# receiver_1.net
KiCad netlist of a schematic drawn in Altium Designer
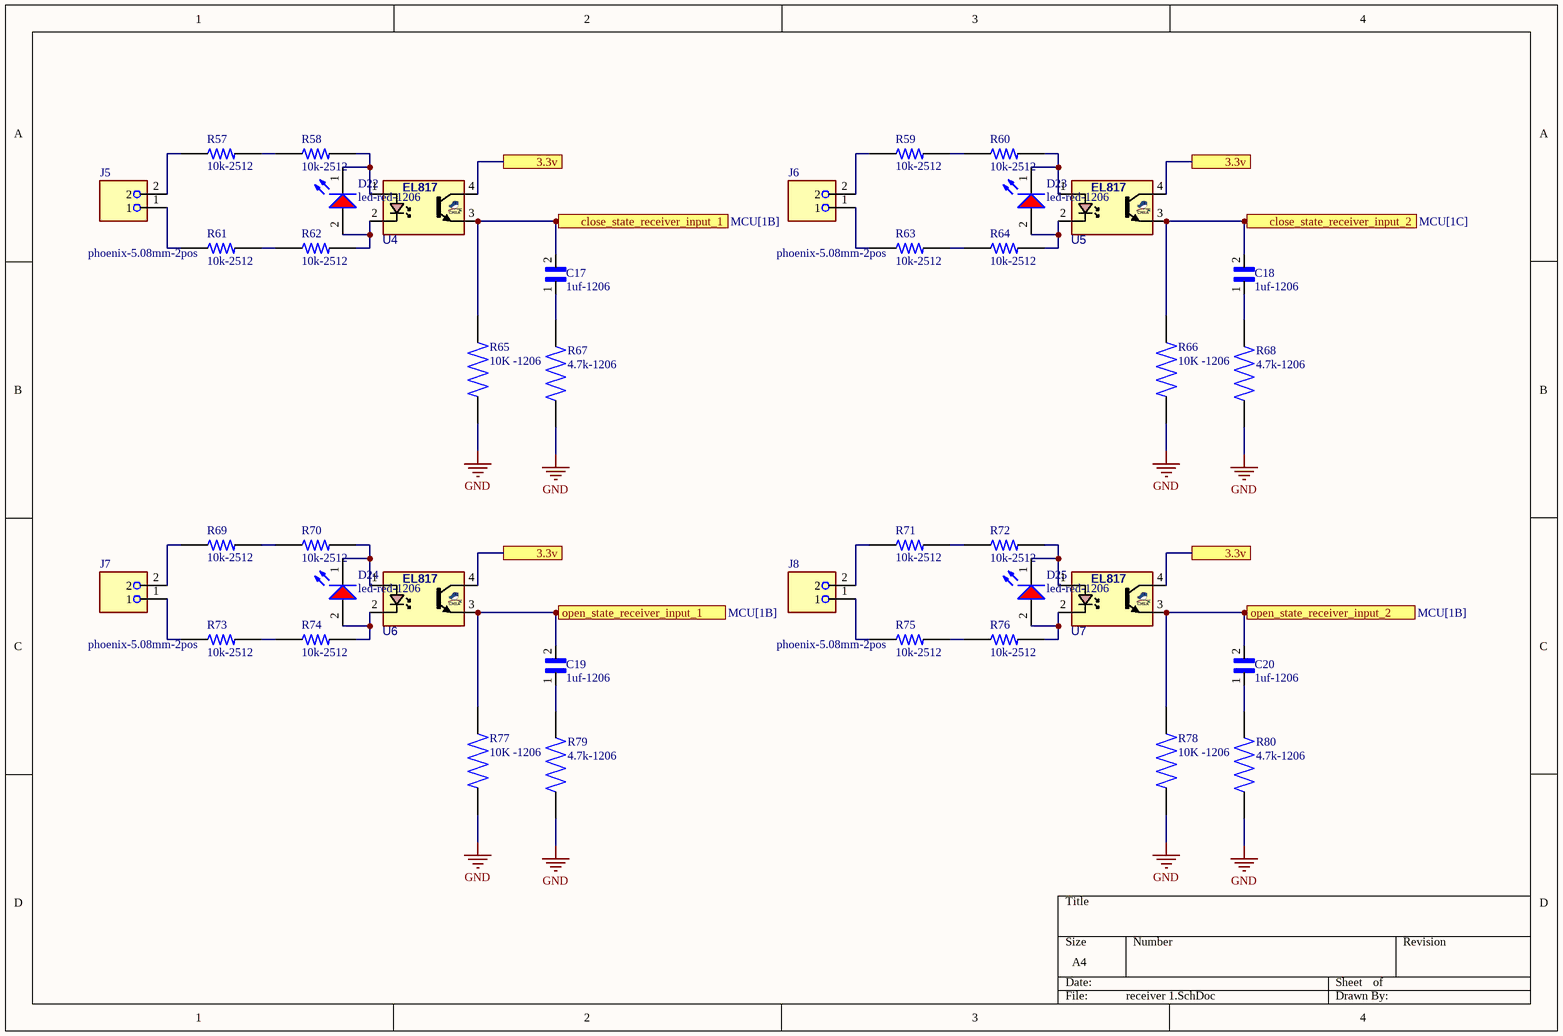
[diagram p0: receiver 1.SchDoc]

(export (version "E")
  (design (tool "Eeschema 10.0.6"))
  (components
    (comp (ref "C17")
      (value "1uf-1206")
      (footprint "CAPC3216X180N")
      (description "1ÂµF Â±20% 50V Ceramic Capacitor X8R 1206 (3216 Metric)")
      (fields (field (name "MF") "TDK") (field (name "MP") "CGA5L3X8R1H105M160AB"))
      (libsource (lib "cap-1206") (part "CGA5L3X8R1H105M160AB"))
    )
    (comp (ref "C18")
      (value "1uf-1206")
      (footprint "CAPC3216X180N")
      (description "1ÂµF Â±20% 50V Ceramic Capacitor X8R 1206 (3216 Metric)")
      (fields (field (name "MF") "TDK") (field (name "MP") "CGA5L3X8R1H105M160AB"))
      (libsource (lib "cap-1206") (part "CGA5L3X8R1H105M160AB"))
    )
    (comp (ref "C19")
      (value "1uf-1206")
      (footprint "CAPC3216X180N")
      (description "1ÂµF Â±20% 50V Ceramic Capacitor X8R 1206 (3216 Metric)")
      (fields (field (name "MF") "TDK") (field (name "MP") "CGA5L3X8R1H105M160AB"))
      (libsource (lib "cap-1206") (part "CGA5L3X8R1H105M160AB"))
    )
    (comp (ref "C20")
      (value "1uf-1206")
      (footprint "CAPC3216X180N")
      (description "1ÂµF Â±20% 50V Ceramic Capacitor X8R 1206 (3216 Metric)")
      (fields (field (name "MF") "TDK") (field (name "MP") "CGA5L3X8R1H105M160AB"))
      (libsource (lib "cap-1206") (part "CGA5L3X8R1H105M160AB"))
    )
    (comp (ref "D22")
      (value "led-red-1206")
      (footprint "WL-SMRW_1206 dome_normal use")
      (description "WL-SMRW Mono-color Reverse mount Waterclear, SMT, size 1206 dome, Red, 2V, 20°")
      (fields
        (field (name "MANUFACTURER PART NUMBER") "156120RS82500")
        (field (name "MANUFACTURER") "Wurth Elektronik")
      )
      (libsource (lib "led-1206") (part "156120RS82500"))
    )
    (comp (ref "D23")
      (value "led-red-1206")
      (footprint "WL-SMRW_1206 dome_normal use")
      (description "WL-SMRW Mono-color Reverse mount Waterclear, SMT, size 1206 dome, Red, 2V, 20°")
      (fields
        (field (name "MANUFACTURER PART NUMBER") "156120RS82500")
        (field (name "MANUFACTURER") "Wurth Elektronik")
      )
      (libsource (lib "led-1206") (part "156120RS82500"))
    )
    (comp (ref "D24")
      (value "led-red-1206")
      (footprint "WL-SMRW_1206 dome_normal use")
      (description "WL-SMRW Mono-color Reverse mount Waterclear, SMT, size 1206 dome, Red, 2V, 20°")
      (fields
        (field (name "MANUFACTURER PART NUMBER") "156120RS82500")
        (field (name "MANUFACTURER") "Wurth Elektronik")
      )
      (libsource (lib "led-1206") (part "156120RS82500"))
    )
    (comp (ref "D25")
      (value "led-red-1206")
      (footprint "WL-SMRW_1206 dome_normal use")
      (description "WL-SMRW Mono-color Reverse mount Waterclear, SMT, size 1206 dome, Red, 2V, 20°")
      (fields
        (field (name "MANUFACTURER PART NUMBER") "156120RS82500")
        (field (name "MANUFACTURER") "Wurth Elektronik")
      )
      (libsource (lib "led-1206") (part "156120RS82500"))
    )
    (comp (ref "J5")
      (value "phoenix-5.08mm-2pos")
      (footprint "PHOENIX_1715721")
      (fields (field (name "MP") "1715721"))
      (libsource (lib "phoenix-2pos") (part "1715721"))
    )
    (comp (ref "J6")
      (value "phoenix-5.08mm-2pos")
      (footprint "PHOENIX_1715721")
      (fields (field (name "MP") "1715721"))
      (libsource (lib "phoenix-2pos") (part "1715721"))
    )
    (comp (ref "J7")
      (value "phoenix-5.08mm-2pos")
      (footprint "PHOENIX_1715721")
      (fields (field (name "MP") "1715721"))
      (libsource (lib "phoenix-2pos") (part "1715721"))
    )
    (comp (ref "J8")
      (value "phoenix-5.08mm-2pos")
      (footprint "PHOENIX_1715721")
      (fields (field (name "MP") "1715721"))
      (libsource (lib "phoenix-2pos") (part "1715721"))
    )
    (comp (ref "R57")
      (value "10k-2512")
      (footprint "RESC6331X70N")
      (description "18 kOhms Â±5% 1.5W Chip Resistor 2512 (6432 Metric) Pulse Withstanding Thick Film")
      (fields (field (name "MF") "TE Connectivity") (field (name "MP") "5-2176246-2"))
      (libsource (lib "resistor-2512") (part "5-2176246-2"))
    )
    (comp (ref "R58")
      (value "10k-2512")
      (footprint "RESC6331X70N")
      (description "18 kOhms Â±5% 1.5W Chip Resistor 2512 (6432 Metric) Pulse Withstanding Thick Film")
      (fields (field (name "MF") "TE Connectivity") (field (name "MP") "5-2176246-2"))
      (libsource (lib "resistor-2512") (part "5-2176246-2"))
    )
    (comp (ref "R59")
      (value "10k-2512")
      (footprint "RESC6331X70N")
      (description "18 kOhms Â±5% 1.5W Chip Resistor 2512 (6432 Metric) Pulse Withstanding Thick Film")
      (fields (field (name "MF") "TE Connectivity") (field (name "MP") "5-2176246-2"))
      (libsource (lib "resistor-2512") (part "5-2176246-2"))
    )
    (comp (ref "R60")
      (value "10k-2512")
      (footprint "RESC6331X70N")
      (description "18 kOhms Â±5% 1.5W Chip Resistor 2512 (6432 Metric) Pulse Withstanding Thick Film")
      (fields (field (name "MF") "TE Connectivity") (field (name "MP") "5-2176246-2"))
      (libsource (lib "resistor-2512") (part "5-2176246-2"))
    )
    (comp (ref "R61")
      (value "10k-2512")
      (footprint "RESC6331X70N")
      (description "18 kOhms Â±5% 1.5W Chip Resistor 2512 (6432 Metric) Pulse Withstanding Thick Film")
      (fields (field (name "MF") "TE Connectivity") (field (name "MP") "5-2176246-2"))
      (libsource (lib "resistor-2512") (part "5-2176246-2"))
    )
    (comp (ref "R62")
      (value "10k-2512")
      (footprint "RESC6331X70N")
      (description "18 kOhms Â±5% 1.5W Chip Resistor 2512 (6432 Metric) Pulse Withstanding Thick Film")
      (fields (field (name "MF") "TE Connectivity") (field (name "MP") "5-2176246-2"))
      (libsource (lib "resistor-2512") (part "5-2176246-2"))
    )
    (comp (ref "R63")
      (value "10k-2512")
      (footprint "RESC6331X70N")
      (description "18 kOhms Â±5% 1.5W Chip Resistor 2512 (6432 Metric) Pulse Withstanding Thick Film")
      (fields (field (name "MF") "TE Connectivity") (field (name "MP") "5-2176246-2"))
      (libsource (lib "resistor-2512") (part "5-2176246-2"))
    )
    (comp (ref "R64")
      (value "10k-2512")
      (footprint "RESC6331X70N")
      (description "18 kOhms Â±5% 1.5W Chip Resistor 2512 (6432 Metric) Pulse Withstanding Thick Film")
      (fields (field (name "MF") "TE Connectivity") (field (name "MP") "5-2176246-2"))
      (libsource (lib "resistor-2512") (part "5-2176246-2"))
    )
    (comp (ref "R65")
      (value "10K -1206")
      (footprint "RESC3015X65N")
      (description "Res Thin Film 1206 10K Ohm 0.1% 1/8W Â±25ppm/Â°C Molded SMD SMD Paper T/R")
      (fields (field (name "MF") "TE Connectivity") (field (name "MP") "CPF1206B10KE1"))
      (libsource (lib "resistor-1206") (part "CPF1206B10KE1"))
    )
    (comp (ref "R66")
      (value "10K -1206")
      (footprint "RESC3015X65N")
      (description "Res Thin Film 1206 10K Ohm 0.1% 1/8W Â±25ppm/Â°C Molded SMD SMD Paper T/R")
      (fields (field (name "MF") "TE Connectivity") (field (name "MP") "CPF1206B10KE1"))
      (libsource (lib "resistor-1206") (part "CPF1206B10KE1"))
    )
    (comp (ref "R67")
      (value "4.7k-1206")
      (footprint "RESC3015X65N")
      (description "Res Thin Film 1206 10K Ohm 0.1% 1/8W Â±25ppm/Â°C Molded SMD SMD Paper T/R")
      (fields (field (name "MF") "TE Connectivity") (field (name "MP") "CPF1206B10KE1"))
      (libsource (lib "resistor-1206") (part "CPF1206B10KE1"))
    )
    (comp (ref "R68")
      (value "4.7k-1206")
      (footprint "RESC3015X65N")
      (description "Res Thin Film 1206 10K Ohm 0.1% 1/8W Â±25ppm/Â°C Molded SMD SMD Paper T/R")
      (fields (field (name "MF") "TE Connectivity") (field (name "MP") "CPF1206B10KE1"))
      (libsource (lib "resistor-1206") (part "CPF1206B10KE1"))
    )
    (comp (ref "R69")
      (value "10k-2512")
      (footprint "RESC6331X70N")
      (description "18 kOhms Â±5% 1.5W Chip Resistor 2512 (6432 Metric) Pulse Withstanding Thick Film")
      (fields (field (name "MF") "TE Connectivity") (field (name "MP") "5-2176246-2"))
      (libsource (lib "resistor-2512") (part "5-2176246-2"))
    )
    (comp (ref "R70")
      (value "10k-2512")
      (footprint "RESC6331X70N")
      (description "18 kOhms Â±5% 1.5W Chip Resistor 2512 (6432 Metric) Pulse Withstanding Thick Film")
      (fields (field (name "MF") "TE Connectivity") (field (name "MP") "5-2176246-2"))
      (libsource (lib "resistor-2512") (part "5-2176246-2"))
    )
    (comp (ref "R71")
      (value "10k-2512")
      (footprint "RESC6331X70N")
      (description "18 kOhms Â±5% 1.5W Chip Resistor 2512 (6432 Metric) Pulse Withstanding Thick Film")
      (fields (field (name "MF") "TE Connectivity") (field (name "MP") "5-2176246-2"))
      (libsource (lib "resistor-2512") (part "5-2176246-2"))
    )
    (comp (ref "R72")
      (value "10k-2512")
      (footprint "RESC6331X70N")
      (description "18 kOhms Â±5% 1.5W Chip Resistor 2512 (6432 Metric) Pulse Withstanding Thick Film")
      (fields (field (name "MF") "TE Connectivity") (field (name "MP") "5-2176246-2"))
      (libsource (lib "resistor-2512") (part "5-2176246-2"))
    )
    (comp (ref "R73")
      (value "10k-2512")
      (footprint "RESC6331X70N")
      (description "18 kOhms Â±5% 1.5W Chip Resistor 2512 (6432 Metric) Pulse Withstanding Thick Film")
      (fields (field (name "MF") "TE Connectivity") (field (name "MP") "5-2176246-2"))
      (libsource (lib "resistor-2512") (part "5-2176246-2"))
    )
    (comp (ref "R74")
      (value "10k-2512")
      (footprint "RESC6331X70N")
      (description "18 kOhms Â±5% 1.5W Chip Resistor 2512 (6432 Metric) Pulse Withstanding Thick Film")
      (fields (field (name "MF") "TE Connectivity") (field (name "MP") "5-2176246-2"))
      (libsource (lib "resistor-2512") (part "5-2176246-2"))
    )
    (comp (ref "R75")
      (value "10k-2512")
      (footprint "RESC6331X70N")
      (description "18 kOhms Â±5% 1.5W Chip Resistor 2512 (6432 Metric) Pulse Withstanding Thick Film")
      (fields (field (name "MF") "TE Connectivity") (field (name "MP") "5-2176246-2"))
      (libsource (lib "resistor-2512") (part "5-2176246-2"))
    )
    (comp (ref "R76")
      (value "10k-2512")
      (footprint "RESC6331X70N")
      (description "18 kOhms Â±5% 1.5W Chip Resistor 2512 (6432 Metric) Pulse Withstanding Thick Film")
      (fields (field (name "MF") "TE Connectivity") (field (name "MP") "5-2176246-2"))
      (libsource (lib "resistor-2512") (part "5-2176246-2"))
    )
    (comp (ref "R77")
      (value "10K -1206")
      (footprint "RESC3015X65N")
      (description "Res Thin Film 1206 10K Ohm 0.1% 1/8W Â±25ppm/Â°C Molded SMD SMD Paper T/R")
      (fields (field (name "MF") "TE Connectivity") (field (name "MP") "CPF1206B10KE1"))
      (libsource (lib "resistor-1206") (part "CPF1206B10KE1"))
    )
    (comp (ref "R78")
      (value "10K -1206")
      (footprint "RESC3015X65N")
      (description "Res Thin Film 1206 10K Ohm 0.1% 1/8W Â±25ppm/Â°C Molded SMD SMD Paper T/R")
      (fields (field (name "MF") "TE Connectivity") (field (name "MP") "CPF1206B10KE1"))
      (libsource (lib "resistor-1206") (part "CPF1206B10KE1"))
    )
    (comp (ref "R79")
      (value "4.7k-1206")
      (footprint "RESC3015X65N")
      (description "Res Thin Film 1206 10K Ohm 0.1% 1/8W Â±25ppm/Â°C Molded SMD SMD Paper T/R")
      (fields (field (name "MF") "TE Connectivity") (field (name "MP") "CPF1206B10KE1"))
      (libsource (lib "resistor-1206") (part "CPF1206B10KE1"))
    )
    (comp (ref "R80")
      (value "4.7k-1206")
      (footprint "RESC3015X65N")
      (description "Res Thin Film 1206 10K Ohm 0.1% 1/8W Â±25ppm/Â°C Molded SMD SMD Paper T/R")
      (fields (field (name "MF") "TE Connectivity") (field (name "MP") "CPF1206B10KE1"))
      (libsource (lib "resistor-1206") (part "CPF1206B10KE1"))
    )
    (comp (ref "U4")
      (value "EL817")
      (footprint "DIP_4SMD")
      (description "OPTOCOUPLER, TRANSISTOR, 4PIN")
      (libsource (lib "optocoupler") (part "OPTC_TR4P_EL817_SMD"))
    )
    (comp (ref "U5")
      (value "EL817")
      (footprint "DIP_4SMD")
      (description "OPTOCOUPLER, TRANSISTOR, 4PIN")
      (libsource (lib "optocoupler") (part "OPTC_TR4P_EL817_SMD"))
    )
    (comp (ref "U6")
      (value "EL817")
      (footprint "DIP_4SMD")
      (description "OPTOCOUPLER, TRANSISTOR, 4PIN")
      (libsource (lib "optocoupler") (part "OPTC_TR4P_EL817_SMD"))
    )
    (comp (ref "U7")
      (value "EL817")
      (footprint "DIP_4SMD")
      (description "OPTOCOUPLER, TRANSISTOR, 4PIN")
      (libsource (lib "optocoupler") (part "OPTC_TR4P_EL817_SMD"))
    )
  )
  (nets
    (net (code "1") (name "/3.3v") (class "Default")
      (node (ref "U4") (pin "4") (pinfunction "C_4") (pintype "passive"))
      (node (ref "U5") (pin "4") (pinfunction "C_4") (pintype "passive"))
      (node (ref "U6") (pin "4") (pinfunction "C_4") (pintype "passive"))
      (node (ref "U7") (pin "4") (pinfunction "C_4") (pintype "passive"))
    )
    (net (code "2") (name "/close_state_receiver_input_1") (class "Default")
      (node (ref "C17") (pin "2") (pinfunction "2_2") (pintype "passive"))
      (node (ref "R65") (pin "2") (pinfunction "2_2") (pintype "passive"))
      (node (ref "U4") (pin "3") (pinfunction "E_3") (pintype "passive"))
    )
    (net (code "3") (name "/close_state_receiver_input_2") (class "Default")
      (node (ref "C18") (pin "2") (pinfunction "2_2") (pintype "passive"))
      (node (ref "R66") (pin "2") (pinfunction "2_2") (pintype "passive"))
      (node (ref "U5") (pin "3") (pinfunction "E_3") (pintype "passive"))
    )
    (net (code "4") (name "/open_state_receiver_input_1") (class "Default")
      (node (ref "C19") (pin "2") (pinfunction "2_2") (pintype "passive"))
      (node (ref "R77") (pin "2") (pinfunction "2_2") (pintype "passive"))
      (node (ref "U6") (pin "3") (pinfunction "E_3") (pintype "passive"))
    )
    (net (code "5") (name "/open_state_receiver_input_2") (class "Default")
      (node (ref "C20") (pin "2") (pinfunction "2_2") (pintype "passive"))
      (node (ref "R78") (pin "2") (pinfunction "2_2") (pintype "passive"))
      (node (ref "U7") (pin "3") (pinfunction "E_3") (pintype "passive"))
    )
    (net (code "6") (name "GND") (class "Default")
      (node (ref "R65") (pin "1") (pinfunction "1_1") (pintype "passive"))
      (node (ref "R66") (pin "1") (pinfunction "1_1") (pintype "passive"))
      (node (ref "R67") (pin "1") (pinfunction "1_1") (pintype "passive"))
      (node (ref "R68") (pin "1") (pinfunction "1_1") (pintype "passive"))
      (node (ref "R77") (pin "1") (pinfunction "1_1") (pintype "passive"))
      (node (ref "R78") (pin "1") (pinfunction "1_1") (pintype "passive"))
      (node (ref "R79") (pin "1") (pinfunction "1_1") (pintype "passive"))
      (node (ref "R80") (pin "1") (pinfunction "1_1") (pintype "passive"))
    )
    (net (code "7") (name "Net-(C17-Pad1)") (class "Default")
      (node (ref "C17") (pin "1") (pinfunction "1_1") (pintype "passive"))
      (node (ref "R67") (pin "2") (pinfunction "2_2") (pintype "passive"))
    )
    (net (code "8") (name "Net-(C18-Pad1)") (class "Default")
      (node (ref "C18") (pin "1") (pinfunction "1_1") (pintype "passive"))
      (node (ref "R68") (pin "2") (pinfunction "2_2") (pintype "passive"))
    )
    (net (code "9") (name "Net-(C19-Pad1)") (class "Default")
      (node (ref "C19") (pin "1") (pinfunction "1_1") (pintype "passive"))
      (node (ref "R79") (pin "2") (pinfunction "2_2") (pintype "passive"))
    )
    (net (code "10") (name "Net-(C20-Pad1)") (class "Default")
      (node (ref "C20") (pin "1") (pinfunction "1_1") (pintype "passive"))
      (node (ref "R80") (pin "2") (pinfunction "2_2") (pintype "passive"))
    )
    (net (code "11") (name "Net-(D22-A)") (class "Default")
      (node (ref "D22") (pin "2") (pinfunction "A_2") (pintype "passive"))
      (node (ref "R62") (pin "2") (pinfunction "2_2") (pintype "passive"))
      (node (ref "U4") (pin "2") (pinfunction "K_2") (pintype "passive"))
    )
    (net (code "12") (name "Net-(D22-K)") (class "Default")
      (node (ref "D22") (pin "1") (pinfunction "K_1") (pintype "passive"))
      (node (ref "R58") (pin "2") (pinfunction "2_2") (pintype "passive"))
      (node (ref "U4") (pin "1") (pinfunction "A_1") (pintype "passive"))
    )
    (net (code "13") (name "Net-(D23-A)") (class "Default")
      (node (ref "D23") (pin "2") (pinfunction "A_2") (pintype "passive"))
      (node (ref "R64") (pin "2") (pinfunction "2_2") (pintype "passive"))
      (node (ref "U5") (pin "2") (pinfunction "K_2") (pintype "passive"))
    )
    (net (code "14") (name "Net-(D23-K)") (class "Default")
      (node (ref "D23") (pin "1") (pinfunction "K_1") (pintype "passive"))
      (node (ref "R60") (pin "2") (pinfunction "2_2") (pintype "passive"))
      (node (ref "U5") (pin "1") (pinfunction "A_1") (pintype "passive"))
    )
    (net (code "15") (name "Net-(D24-A)") (class "Default")
      (node (ref "D24") (pin "2") (pinfunction "A_2") (pintype "passive"))
      (node (ref "R74") (pin "2") (pinfunction "2_2") (pintype "passive"))
      (node (ref "U6") (pin "2") (pinfunction "K_2") (pintype "passive"))
    )
    (net (code "16") (name "Net-(D24-K)") (class "Default")
      (node (ref "D24") (pin "1") (pinfunction "K_1") (pintype "passive"))
      (node (ref "R70") (pin "2") (pinfunction "2_2") (pintype "passive"))
      (node (ref "U6") (pin "1") (pinfunction "A_1") (pintype "passive"))
    )
    (net (code "17") (name "Net-(D25-A)") (class "Default")
      (node (ref "D25") (pin "2") (pinfunction "A_2") (pintype "passive"))
      (node (ref "R76") (pin "2") (pinfunction "2_2") (pintype "passive"))
      (node (ref "U7") (pin "2") (pinfunction "K_2") (pintype "passive"))
    )
    (net (code "18") (name "Net-(D25-K)") (class "Default")
      (node (ref "D25") (pin "1") (pinfunction "K_1") (pintype "passive"))
      (node (ref "R72") (pin "2") (pinfunction "2_2") (pintype "passive"))
      (node (ref "U7") (pin "1") (pinfunction "A_1") (pintype "passive"))
    )
    (net (code "19") (name "Net-(J5-Pad1)") (class "Default")
      (node (ref "J5") (pin "1") (pinfunction "1_1") (pintype "passive"))
      (node (ref "R61") (pin "1") (pinfunction "1_1") (pintype "passive"))
    )
    (net (code "20") (name "Net-(J5-Pad2)") (class "Default")
      (node (ref "J5") (pin "2") (pinfunction "2_2") (pintype "passive"))
      (node (ref "R57") (pin "1") (pinfunction "1_1") (pintype "passive"))
    )
    (net (code "21") (name "Net-(J6-Pad1)") (class "Default")
      (node (ref "J6") (pin "1") (pinfunction "1_1") (pintype "passive"))
      (node (ref "R63") (pin "1") (pinfunction "1_1") (pintype "passive"))
    )
    (net (code "22") (name "Net-(J6-Pad2)") (class "Default")
      (node (ref "J6") (pin "2") (pinfunction "2_2") (pintype "passive"))
      (node (ref "R59") (pin "1") (pinfunction "1_1") (pintype "passive"))
    )
    (net (code "23") (name "Net-(J7-Pad1)") (class "Default")
      (node (ref "J7") (pin "1") (pinfunction "1_1") (pintype "passive"))
      (node (ref "R73") (pin "1") (pinfunction "1_1") (pintype "passive"))
    )
    (net (code "24") (name "Net-(J7-Pad2)") (class "Default")
      (node (ref "J7") (pin "2") (pinfunction "2_2") (pintype "passive"))
      (node (ref "R69") (pin "1") (pinfunction "1_1") (pintype "passive"))
    )
    (net (code "25") (name "Net-(J8-Pad1)") (class "Default")
      (node (ref "J8") (pin "1") (pinfunction "1_1") (pintype "passive"))
      (node (ref "R75") (pin "1") (pinfunction "1_1") (pintype "passive"))
    )
    (net (code "26") (name "Net-(J8-Pad2)") (class "Default")
      (node (ref "J8") (pin "2") (pinfunction "2_2") (pintype "passive"))
      (node (ref "R71") (pin "1") (pinfunction "1_1") (pintype "passive"))
    )
    (net (code "27") (name "Net-(R57-Pad2)") (class "Default")
      (node (ref "R57") (pin "2") (pinfunction "2_2") (pintype "passive"))
      (node (ref "R58") (pin "1") (pinfunction "1_1") (pintype "passive"))
    )
    (net (code "28") (name "Net-(R59-Pad2)") (class "Default")
      (node (ref "R59") (pin "2") (pinfunction "2_2") (pintype "passive"))
      (node (ref "R60") (pin "1") (pinfunction "1_1") (pintype "passive"))
    )
    (net (code "29") (name "Net-(R61-Pad2)") (class "Default")
      (node (ref "R61") (pin "2") (pinfunction "2_2") (pintype "passive"))
      (node (ref "R62") (pin "1") (pinfunction "1_1") (pintype "passive"))
    )
    (net (code "30") (name "Net-(R63-Pad2)") (class "Default")
      (node (ref "R63") (pin "2") (pinfunction "2_2") (pintype "passive"))
      (node (ref "R64") (pin "1") (pinfunction "1_1") (pintype "passive"))
    )
    (net (code "31") (name "Net-(R69-Pad2)") (class "Default")
      (node (ref "R69") (pin "2") (pinfunction "2_2") (pintype "passive"))
      (node (ref "R70") (pin "1") (pinfunction "1_1") (pintype "passive"))
    )
    (net (code "32") (name "Net-(R71-Pad2)") (class "Default")
      (node (ref "R71") (pin "2") (pinfunction "2_2") (pintype "passive"))
      (node (ref "R72") (pin "1") (pinfunction "1_1") (pintype "passive"))
    )
    (net (code "33") (name "Net-(R73-Pad2)") (class "Default")
      (node (ref "R73") (pin "2") (pinfunction "2_2") (pintype "passive"))
      (node (ref "R74") (pin "1") (pinfunction "1_1") (pintype "passive"))
    )
    (net (code "34") (name "Net-(R75-Pad2)") (class "Default")
      (node (ref "R75") (pin "2") (pinfunction "2_2") (pintype "passive"))
      (node (ref "R76") (pin "1") (pinfunction "1_1") (pintype "passive"))
    )
  )
)
